# cat_detector.net
KiCad netlist of a schematic drawn in EAGLE
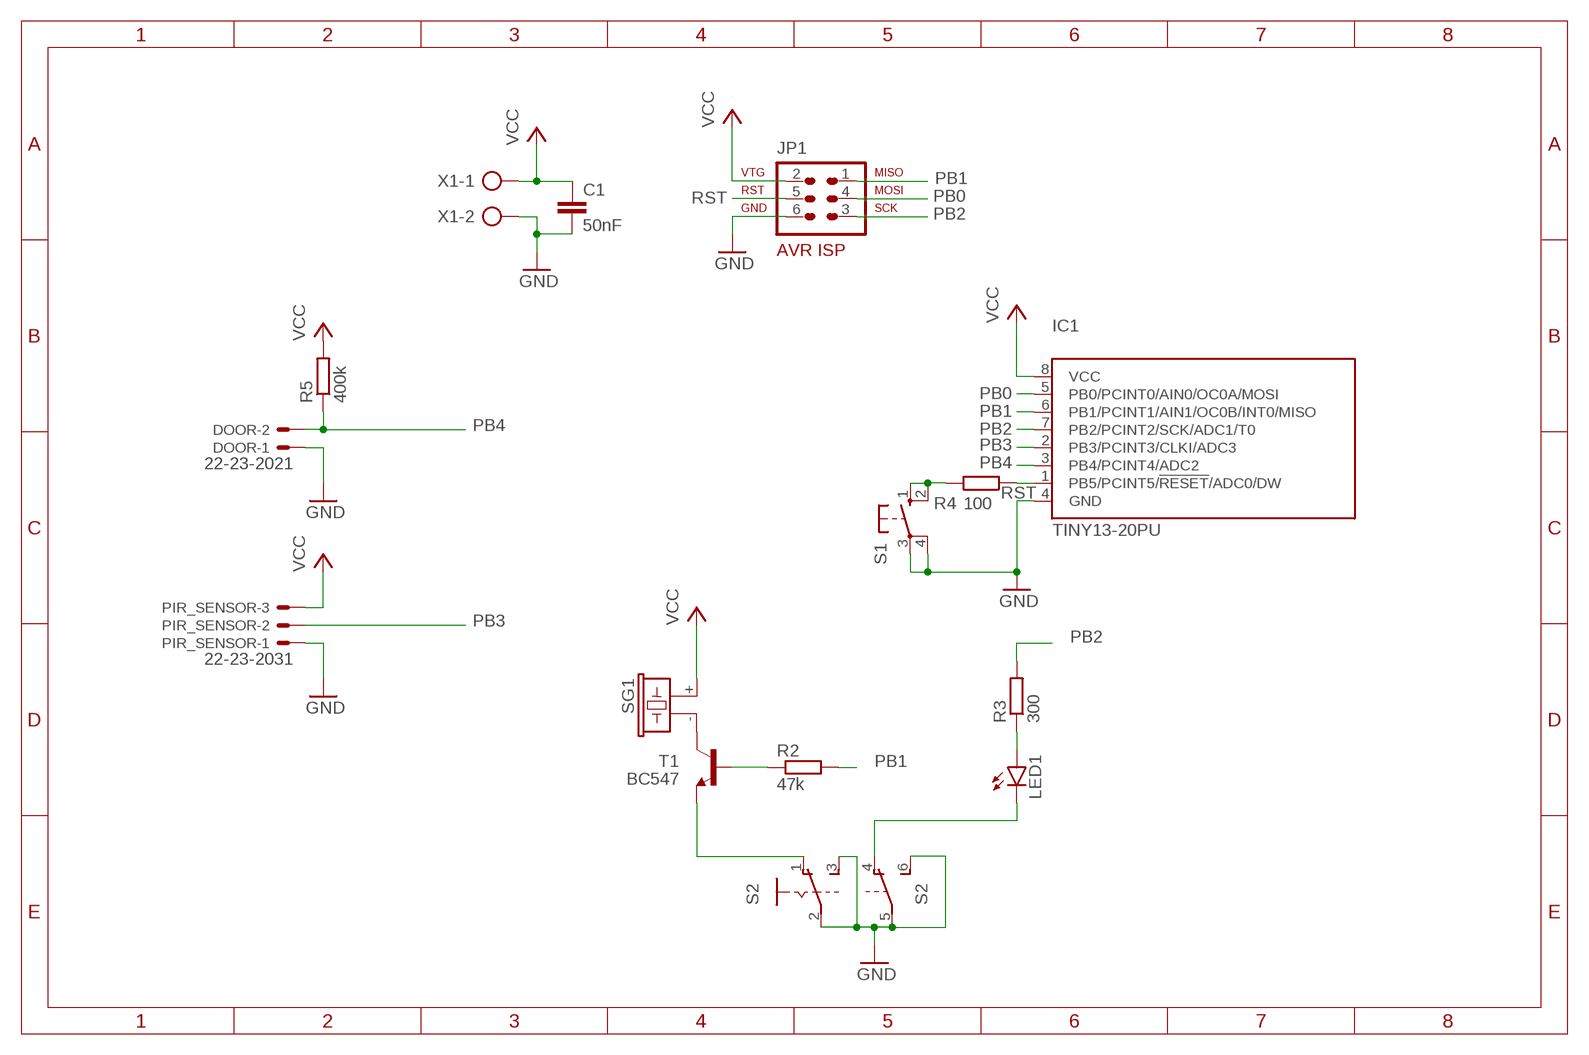
[diagram p0: schematic, sheet 1]

(export (version "E")
  (design (tool "Eeschema 10.0.6"))
  (components
    (comp (ref "C1")
      (value "50nF")
      (footprint "eagle-import:C2.5-2")
      (libsource (lib "eagle-import") (part "C2.5/2"))
    )
    (comp (ref "DOOR")
      (value "22-23-2021")
      (footprint "eagle-import:22-23-2021")
      (fields (field (name "MF") "MOLEX"))
      (libsource (lib "eagle-import") (part "22-23-2021"))
    )
    (comp (ref "IC1")
      (value "TINY13-20PU")
      (footprint "eagle-import:DIL08")
      (fields (field (name "MPN") "ATTINY13-20PU"))
      (libsource (lib "eagle-import") (part "TINY13PU-20"))
    )
    (comp (ref "JP1")
      (value "AVR-ISP-6")
      (footprint "eagle-import:AVR-ISP-6")
      (libsource (lib "eagle-import") (part "AVR-ISP-6"))
    )
    (comp (ref "LED1")
      (value "LED5MM")
      (footprint "eagle-import:LED5MM")
      (libsource (lib "eagle-import") (part "LED5MM"))
    )
    (comp (ref "PIR_SENSOR")
      (value "22-23-2031")
      (footprint "eagle-import:22-23-2031")
      (fields (field (name "MF") "MOLEX"))
      (libsource (lib "eagle-import") (part "22-23-2031"))
    )
    (comp (ref "R2")
      (value "47k")
      (footprint "eagle-import:0204_7")
      (libsource (lib "eagle-import") (part "R-EU_0204/7"))
    )
    (comp (ref "R3")
      (value "300")
      (footprint "eagle-import:0204_7")
      (libsource (lib "eagle-import") (part "R-EU_0204/7"))
    )
    (comp (ref "R4")
      (value "100")
      (footprint "eagle-import:0204_7")
      (libsource (lib "eagle-import") (part "R-EU_0204/7"))
    )
    (comp (ref "R5")
      (value "400k")
      (footprint "eagle-import:0204_7")
      (libsource (lib "eagle-import") (part "R-EU_0204/7"))
    )
    (comp (ref "S1")
      (value "10-XX")
      (footprint "eagle-import:B3F-10XX")
      (fields (field (name "MPN") "B3F-1000"))
      (libsource (lib "eagle-import") (part "10-XX"))
    )
    (comp (ref "S2")
      (value "A68-A31")
      (footprint "eagle-import:A68-A31")
      (libsource (lib "eagle-import") (part "A68-A31"))
    )
    (comp (ref "SG1")
      (value "F/CM12P")
      (footprint "eagle-import:F_CM12P")
      (libsource (lib "eagle-import") (part "F/CM12P"))
    )
    (comp (ref "T1")
      (value "BC547")
      (footprint "eagle-import:TO92")
      (libsource (lib "eagle-import") (part "BC547"))
    )
    (comp (ref "X1")
      (value "CON-PTR500_AK300/2")
      (footprint "eagle-import:CON-PTR500_AK300_2")
      (libsource (lib "eagle-import") (part "CON-PTR500_AK300/2"))
    )
  )
  (nets
    (net (code "1") (name "/PB0") (class "Default")
      (node (ref "IC1") (pin "5") (pinfunction "PB0/PCINT0/AIN0/OC0A/MOSI_5") (pintype "bidirectional"))
      (node (ref "JP1") (pin "4") (pinfunction "4_4") (pintype "passive"))
    )
    (net (code "2") (name "/PB1") (class "Default")
      (node (ref "IC1") (pin "6") (pinfunction "PB1/PCINT1/AIN1/OC0B/INT0/MISO_6") (pintype "bidirectional"))
      (node (ref "JP1") (pin "1") (pinfunction "1_1") (pintype "passive"))
      (node (ref "R2") (pin "2") (pinfunction "2_2") (pintype "passive"))
    )
    (net (code "3") (name "/PB2") (class "Default")
      (node (ref "IC1") (pin "7") (pinfunction "PB2/PCINT2/SCK/ADC1/T0_7") (pintype "bidirectional"))
      (node (ref "JP1") (pin "3") (pinfunction "3_3") (pintype "passive"))
      (node (ref "R3") (pin "2") (pinfunction "2_2") (pintype "passive"))
    )
    (net (code "4") (name "/PB3") (class "Default")
      (node (ref "IC1") (pin "2") (pinfunction "PB3/PCINT3/CLKI/ADC3_2") (pintype "bidirectional"))
      (node (ref "PIR_SENSOR") (pin "2") (pinfunction "S_2") (pintype "passive"))
    )
    (net (code "5") (name "/PB4") (class "Default")
      (node (ref "DOOR") (pin "2") (pinfunction "S_2") (pintype "passive"))
      (node (ref "IC1") (pin "3") (pinfunction "PB4/PCINT4/ADC2_3") (pintype "bidirectional"))
      (node (ref "R5") (pin "1") (pinfunction "1_1") (pintype "passive"))
    )
    (net (code "6") (name "/RST") (class "Default")
      (node (ref "IC1") (pin "1") (pinfunction "PB5/PCINT5/~{RESET}/ADC0/DW_1") (pintype "bidirectional"))
      (node (ref "JP1") (pin "5") (pinfunction "5_5") (pintype "passive"))
      (node (ref "R4") (pin "1") (pinfunction "1_1") (pintype "passive"))
    )
    (net (code "7") (name "GND") (class "Default")
      (node (ref "C1") (pin "2") (pinfunction "2_2") (pintype "passive"))
      (node (ref "DOOR") (pin "1") (pinfunction "S_1") (pintype "passive"))
      (node (ref "IC1") (pin "4") (pinfunction "GND_4") (pintype "power_in"))
      (node (ref "JP1") (pin "6") (pinfunction "6_6") (pintype "passive"))
      (node (ref "PIR_SENSOR") (pin "1") (pinfunction "S_1") (pintype "passive"))
      (node (ref "S1") (pin "3") (pinfunction "P_3") (pintype "passive"))
      (node (ref "S1") (pin "4") (pinfunction "P1_4") (pintype "passive"))
      (node (ref "S2") (pin "2") (pinfunction "P_2") (pintype "passive"))
      (node (ref "S2") (pin "3") (pinfunction "S_3") (pintype "passive"))
      (node (ref "S2") (pin "5") (pinfunction "P_5") (pintype "passive"))
      (node (ref "S2") (pin "6") (pinfunction "S_6") (pintype "passive"))
      (node (ref "X1") (pin "2") (pinfunction "KL_2") (pintype "passive"))
    )
    (net (code "8") (name "Net-(LED1-C)") (class "Default")
      (node (ref "LED1") (pin "K") (pinfunction "C_K") (pintype "passive"))
      (node (ref "S2") (pin "4") (pinfunction "O_4") (pintype "passive"))
    )
    (net (code "9") (name "Net-(LED1-PadA)") (class "Default")
      (node (ref "LED1") (pin "A") (pinfunction "A_A") (pintype "passive"))
      (node (ref "R3") (pin "1") (pinfunction "1_1") (pintype "passive"))
    )
    (net (code "10") (name "Net-(S1-S)") (class "Default")
      (node (ref "R4") (pin "2") (pinfunction "2_2") (pintype "passive"))
      (node (ref "S1") (pin "1") (pinfunction "S_1") (pintype "passive"))
      (node (ref "S1") (pin "2") (pinfunction "S1_2") (pintype "passive"))
    )
    (net (code "11") (name "Net-(S2A-O)") (class "Default")
      (node (ref "S2") (pin "1") (pinfunction "O_1") (pintype "passive"))
      (node (ref "T1") (pin "1") (pinfunction "E_1") (pintype "passive"))
    )
    (net (code "12") (name "Net-(SG1-2)") (class "Default")
      (node (ref "SG1") (pin "-") (pinfunction "2_-") (pintype "passive"))
      (node (ref "T1") (pin "3") (pinfunction "C_3") (pintype "passive"))
    )
    (net (code "13") (name "Net-(T1-B)") (class "Default")
      (node (ref "R2") (pin "1") (pinfunction "1_1") (pintype "passive"))
      (node (ref "T1") (pin "2") (pinfunction "B_2") (pintype "passive"))
    )
    (net (code "14") (name "VCC") (class "Default")
      (node (ref "C1") (pin "1") (pinfunction "1_1") (pintype "passive"))
      (node (ref "IC1") (pin "8") (pinfunction "VCC_8") (pintype "power_in"))
      (node (ref "JP1") (pin "2") (pinfunction "2_2") (pintype "passive"))
      (node (ref "PIR_SENSOR") (pin "3") (pinfunction "S_3") (pintype "passive"))
      (node (ref "R5") (pin "2") (pinfunction "2_2") (pintype "passive"))
      (node (ref "SG1") (pin "+") (pinfunction "1_+") (pintype "passive"))
      (node (ref "X1") (pin "1") (pinfunction "KL_1") (pintype "passive"))
    )
  )
)
